# FINALMOTHERBOARD__morefinal.net
KiCad netlist of a schematic drawn in EAGLE
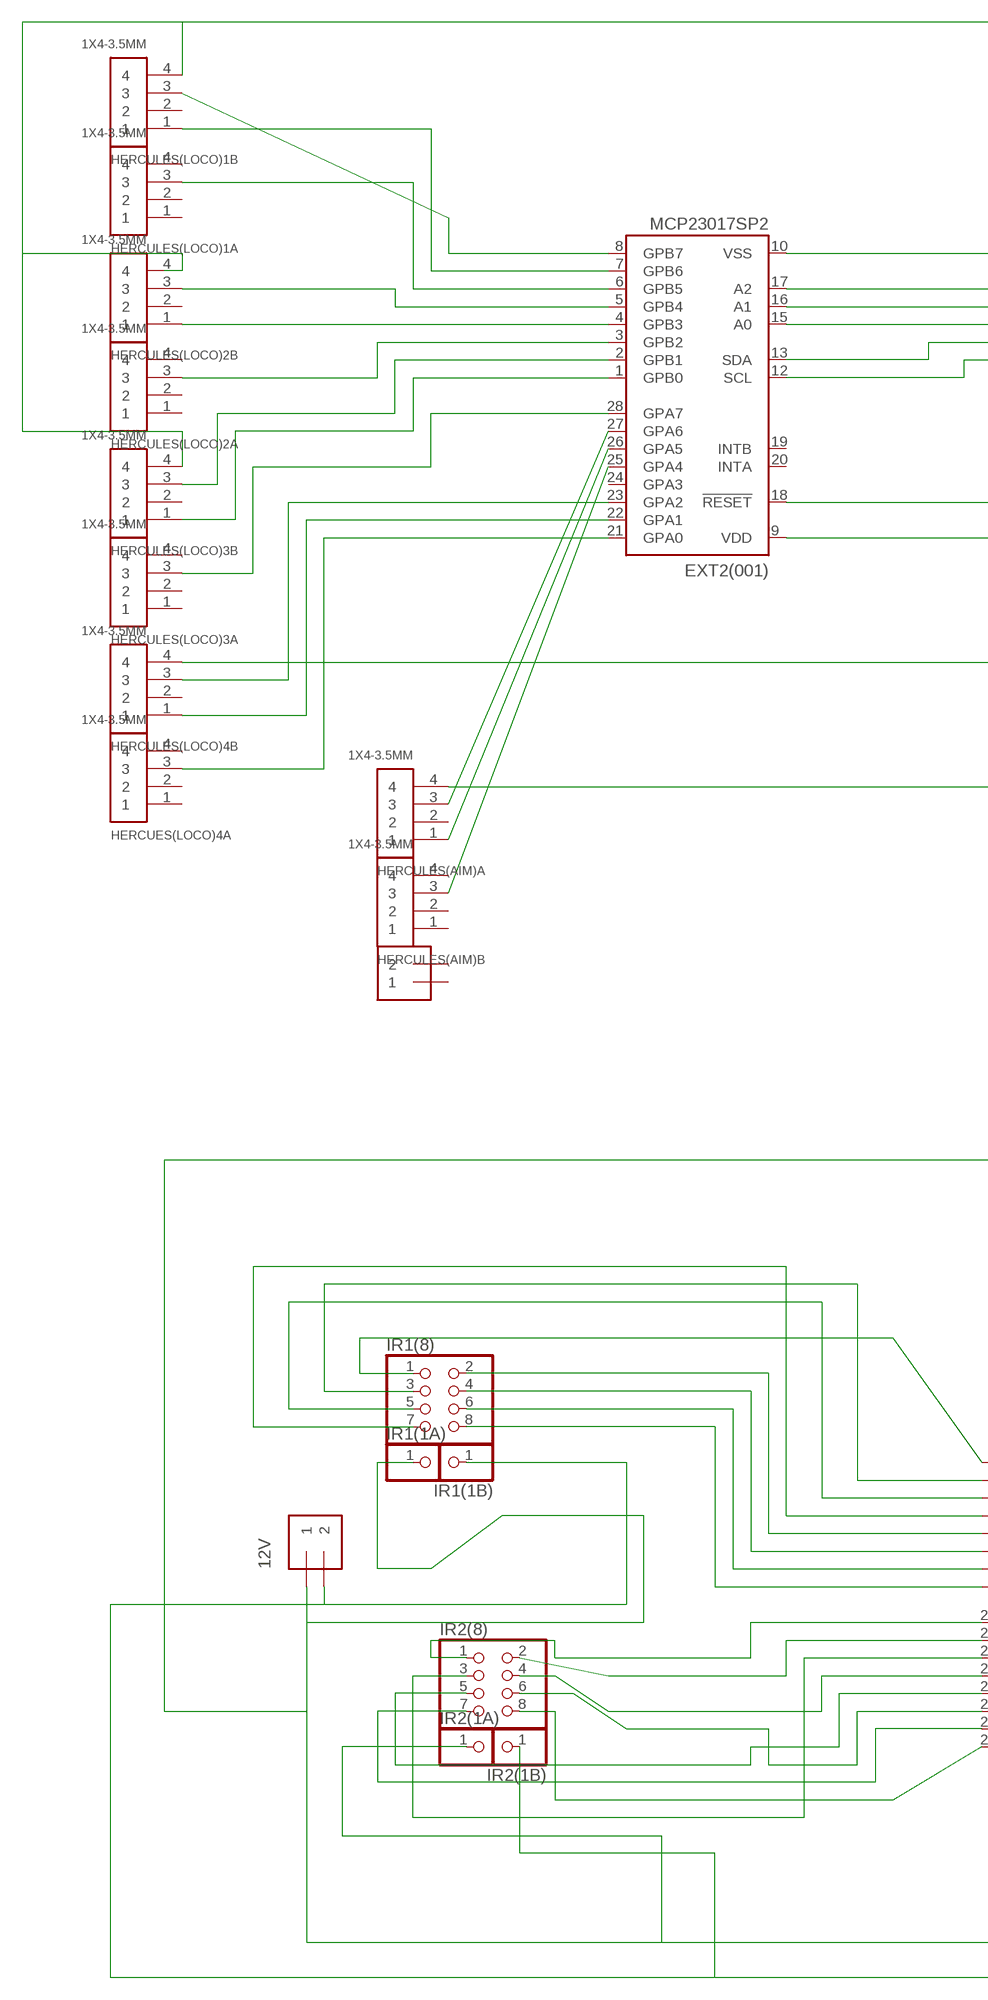
[diagram p0: schematic, sheet 1, part 1 of 2]
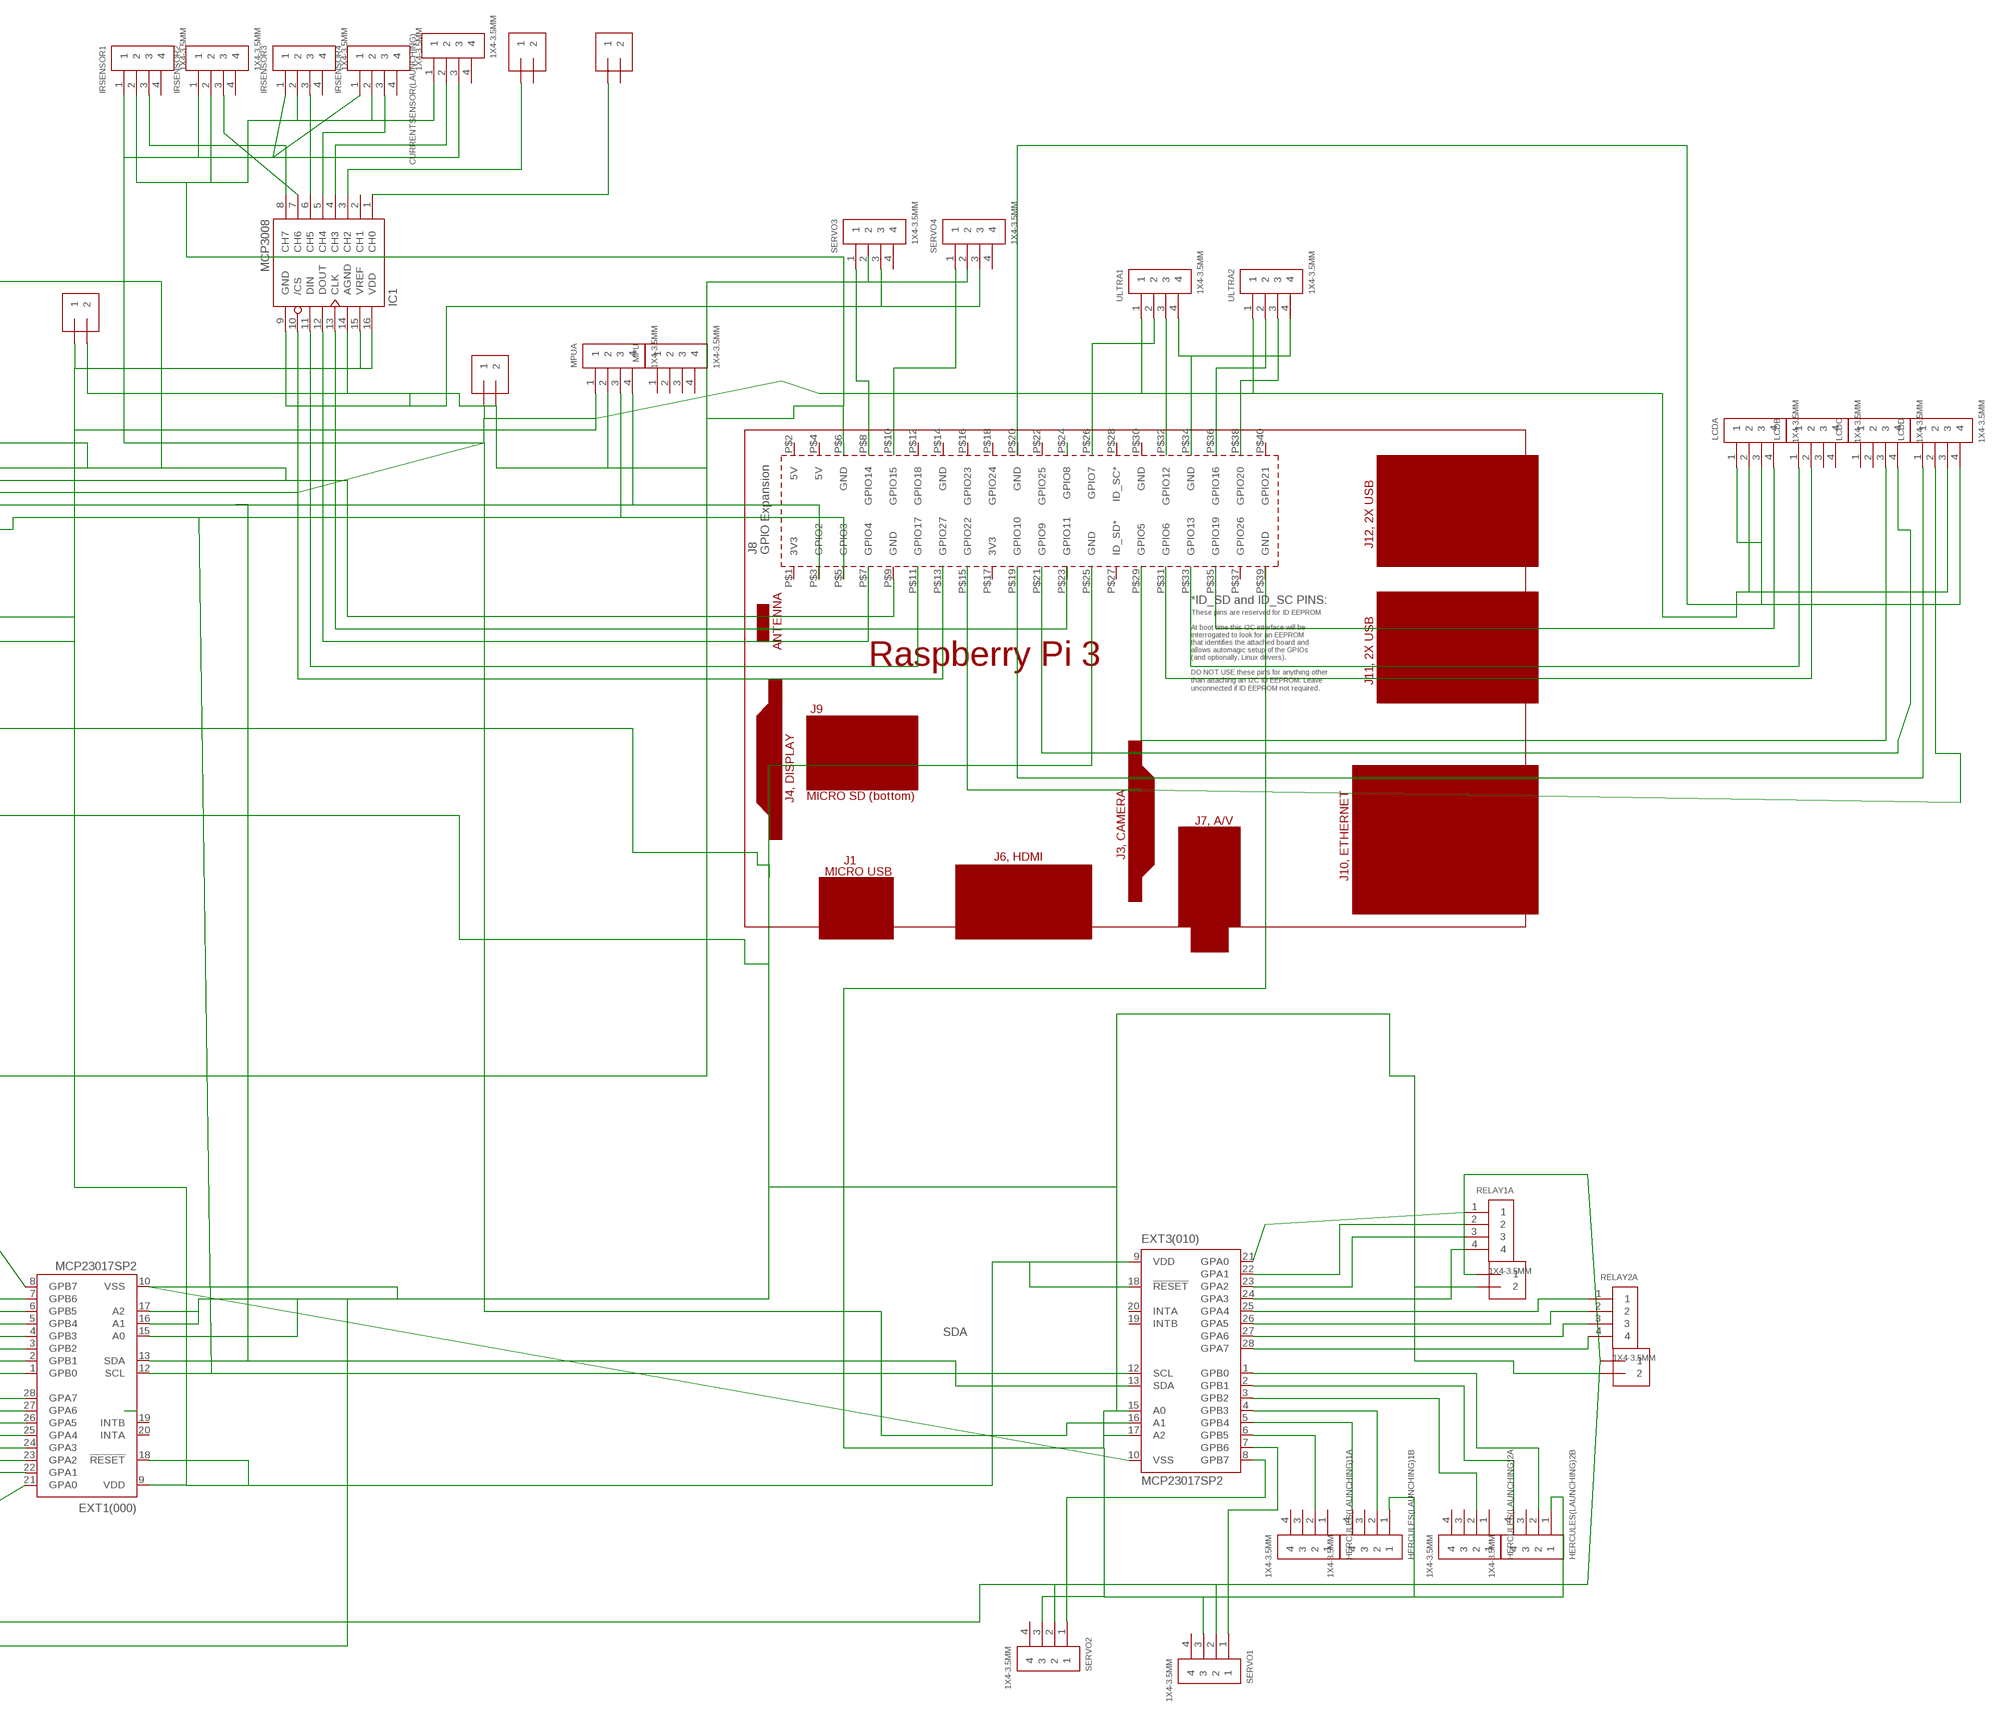
[diagram p1: schematic, sheet 1, part 2 of 2]

(export (version "E")
  (design (tool "Eeschema 10.0.6"))
  (components
    (comp (ref "3.3V")
      (value "1X2-3.5MM")
      (footprint "eagle-import:1X2-3.5MM")
      (libsource (lib "eagle-import") (part "1X2-3.5MM"))
    )
    (comp (ref "5V")
      (value "1X2-3.5MM")
      (footprint "eagle-import:1X2-3.5MM")
      (libsource (lib "eagle-import") (part "1X2-3.5MM"))
    )
    (comp (ref "12V")
      (value "1X2-3.5MM")
      (footprint "eagle-import:1X2-3.5MM")
      (libsource (lib "eagle-import") (part "1X2-3.5MM"))
    )
    (comp (ref "CURRENTSENSOR(LAUNCHING)")
      (value "1X4-3.5MM")
      (footprint "eagle-import:1X04-3.5MM")
      (libsource (lib "eagle-import") (part "1X4-3.5MM"))
    )
    (comp (ref "EXT1(000)")
      (value "MCP23017SP2")
      (footprint "eagle-import:DIL28-3-ROUND")
      (libsource (lib "eagle-import") (part "MCP23017SP2"))
    )
    (comp (ref "EXT2(001)")
      (value "MCP23017SP2")
      (footprint "eagle-import:DIL28-3-ROUND")
      (libsource (lib "eagle-import") (part "MCP23017SP2"))
    )
    (comp (ref "EXT3(010)")
      (value "MCP23017SP2")
      (footprint "eagle-import:DIL28-3-ROUND")
      (libsource (lib "eagle-import") (part "MCP23017SP2"))
    )
    (comp (ref "HERCUES(LOCO)4A")
      (value "1X4-3.5MM")
      (footprint "eagle-import:1X04-3.5MM")
      (libsource (lib "eagle-import") (part "1X4-3.5MM"))
    )
    (comp (ref "HERCULES(AIM)A")
      (value "1X4-3.5MM")
      (footprint "eagle-import:1X04-3.5MM")
      (libsource (lib "eagle-import") (part "1X4-3.5MM"))
    )
    (comp (ref "HERCULES(AIM)B")
      (value "1X4-3.5MM")
      (footprint "eagle-import:1X04-3.5MM")
      (libsource (lib "eagle-import") (part "1X4-3.5MM"))
    )
    (comp (ref "HERCULES(AIM)C")
      (value "1X2-3.5MM")
      (footprint "eagle-import:1X2-3.5MM")
      (libsource (lib "eagle-import") (part "1X2-3.5MM"))
    )
    (comp (ref "HERCULES(LAUNCHING)1A")
      (value "1X4-3.5MM")
      (footprint "eagle-import:1X04-3.5MM")
      (libsource (lib "eagle-import") (part "1X4-3.5MM"))
    )
    (comp (ref "HERCULES(LAUNCHING)1B")
      (value "1X4-3.5MM")
      (footprint "eagle-import:1X04-3.5MM")
      (libsource (lib "eagle-import") (part "1X4-3.5MM"))
    )
    (comp (ref "HERCULES(LAUNCHING)2A")
      (value "1X4-3.5MM")
      (footprint "eagle-import:1X04-3.5MM")
      (libsource (lib "eagle-import") (part "1X4-3.5MM"))
    )
    (comp (ref "HERCULES(LAUNCHING)2B")
      (value "1X4-3.5MM")
      (footprint "eagle-import:1X04-3.5MM")
      (libsource (lib "eagle-import") (part "1X4-3.5MM"))
    )
    (comp (ref "HERCULES(LOCO)1A")
      (value "1X4-3.5MM")
      (footprint "eagle-import:1X04-3.5MM")
      (libsource (lib "eagle-import") (part "1X4-3.5MM"))
    )
    (comp (ref "HERCULES(LOCO)1B")
      (value "1X4-3.5MM")
      (footprint "eagle-import:1X04-3.5MM")
      (libsource (lib "eagle-import") (part "1X4-3.5MM"))
    )
    (comp (ref "HERCULES(LOCO)2A")
      (value "1X4-3.5MM")
      (footprint "eagle-import:1X04-3.5MM")
      (libsource (lib "eagle-import") (part "1X4-3.5MM"))
    )
    (comp (ref "HERCULES(LOCO)2B")
      (value "1X4-3.5MM")
      (footprint "eagle-import:1X04-3.5MM")
      (libsource (lib "eagle-import") (part "1X4-3.5MM"))
    )
    (comp (ref "HERCULES(LOCO)3A")
      (value "1X4-3.5MM")
      (footprint "eagle-import:1X04-3.5MM")
      (libsource (lib "eagle-import") (part "1X4-3.5MM"))
    )
    (comp (ref "HERCULES(LOCO)3B")
      (value "1X4-3.5MM")
      (footprint "eagle-import:1X04-3.5MM")
      (libsource (lib "eagle-import") (part "1X4-3.5MM"))
    )
    (comp (ref "HERCULES(LOCO)4B")
      (value "1X4-3.5MM")
      (footprint "eagle-import:1X04-3.5MM")
      (libsource (lib "eagle-import") (part "1X4-3.5MM"))
    )
    (comp (ref "IC1")
      (value "MCP3008")
      (footprint "eagle-import:DIL16")
      (libsource (lib "eagle-import") (part "MCP3008"))
    )
    (comp (ref "IR(LOCO)1ANALOG")
      (value "1X2-3.5MM")
      (footprint "eagle-import:1X2-3.5MM")
      (libsource (lib "eagle-import") (part "1X2-3.5MM"))
    )
    (comp (ref "IR(LOCO)2ANALOG")
      (value "1X2-3.5MM")
      (footprint "eagle-import:1X2-3.5MM")
      (libsource (lib "eagle-import") (part "1X2-3.5MM"))
    )
    (comp (ref "IR1(1A)")
      (value "PINHD-1X1")
      (footprint "eagle-import:1X01")
      (libsource (lib "eagle-import") (part "PINHD-1X1"))
    )
    (comp (ref "IR1(1B)")
      (value "PINHD-1X1")
      (footprint "eagle-import:1X01")
      (libsource (lib "eagle-import") (part "PINHD-1X1"))
    )
    (comp (ref "IR1(8)")
      (value "PINHD-2X4")
      (footprint "eagle-import:2X04")
      (libsource (lib "eagle-import") (part "PINHD-2X4"))
    )
    (comp (ref "IR2(1A)")
      (value "PINHD-1X1")
      (footprint "eagle-import:1X01")
      (libsource (lib "eagle-import") (part "PINHD-1X1"))
    )
    (comp (ref "IR2(1B)")
      (value "PINHD-1X1")
      (footprint "eagle-import:1X01")
      (libsource (lib "eagle-import") (part "PINHD-1X1"))
    )
    (comp (ref "IR2(8)")
      (value "PINHD-2X4")
      (footprint "eagle-import:2X04")
      (libsource (lib "eagle-import") (part "PINHD-2X4"))
    )
    (comp (ref "IRSENSOR1")
      (value "1X4-3.5MM")
      (footprint "eagle-import:1X04-3.5MM")
      (libsource (lib "eagle-import") (part "1X4-3.5MM"))
    )
    (comp (ref "IRSENSOR2")
      (value "1X4-3.5MM")
      (footprint "eagle-import:1X04-3.5MM")
      (libsource (lib "eagle-import") (part "1X4-3.5MM"))
    )
    (comp (ref "IRSENSOR3")
      (value "1X4-3.5MM")
      (footprint "eagle-import:1X04-3.5MM")
      (libsource (lib "eagle-import") (part "1X4-3.5MM"))
    )
    (comp (ref "IRSENSOR4")
      (value "1X4-3.5MM")
      (footprint "eagle-import:1X04-3.5MM")
      (libsource (lib "eagle-import") (part "1X4-3.5MM"))
    )
    (comp (ref "LCDA")
      (value "1X4-3.5MM")
      (footprint "eagle-import:1X04-3.5MM")
      (libsource (lib "eagle-import") (part "1X4-3.5MM"))
    )
    (comp (ref "LCDB")
      (value "1X4-3.5MM")
      (footprint "eagle-import:1X04-3.5MM")
      (libsource (lib "eagle-import") (part "1X4-3.5MM"))
    )
    (comp (ref "LCDC")
      (value "1X4-3.5MM")
      (footprint "eagle-import:1X04-3.5MM")
      (libsource (lib "eagle-import") (part "1X4-3.5MM"))
    )
    (comp (ref "LCDD")
      (value "1X4-3.5MM")
      (footprint "eagle-import:1X04-3.5MM")
      (libsource (lib "eagle-import") (part "1X4-3.5MM"))
    )
    (comp (ref "MPU")
      (value "1X4-3.5MM")
      (footprint "eagle-import:1X04-3.5MM")
      (libsource (lib "eagle-import") (part "1X4-3.5MM"))
    )
    (comp (ref "MPUA")
      (value "1X4-3.5MM")
      (footprint "eagle-import:1X04-3.5MM")
      (libsource (lib "eagle-import") (part "1X4-3.5MM"))
    )
    (comp (ref "PCB1")
      (value "RPI3")
      (footprint "eagle-import:RPI3")
      (libsource (lib "eagle-import") (part "RPI3"))
    )
    (comp (ref "RELAY1A")
      (value "1X4-3.5MM")
      (footprint "eagle-import:1X04-3.5MM")
      (libsource (lib "eagle-import") (part "1X4-3.5MM"))
    )
    (comp (ref "RELAY1B")
      (value "1X2-3.5MM")
      (footprint "eagle-import:1X2-3.5MM")
      (libsource (lib "eagle-import") (part "1X2-3.5MM"))
    )
    (comp (ref "RELAY2A")
      (value "1X4-3.5MM")
      (footprint "eagle-import:1X04-3.5MM")
      (libsource (lib "eagle-import") (part "1X4-3.5MM"))
    )
    (comp (ref "RELAY2B")
      (value "1X2-3.5MM")
      (footprint "eagle-import:1X2-3.5MM")
      (libsource (lib "eagle-import") (part "1X2-3.5MM"))
    )
    (comp (ref "SERVO1")
      (value "1X4-3.5MM")
      (footprint "eagle-import:1X04-3.5MM")
      (libsource (lib "eagle-import") (part "1X4-3.5MM"))
    )
    (comp (ref "SERVO2")
      (value "1X4-3.5MM")
      (footprint "eagle-import:1X04-3.5MM")
      (libsource (lib "eagle-import") (part "1X4-3.5MM"))
    )
    (comp (ref "SERVO3")
      (value "1X4-3.5MM")
      (footprint "eagle-import:1X04-3.5MM")
      (libsource (lib "eagle-import") (part "1X4-3.5MM"))
    )
    (comp (ref "SERVO4")
      (value "1X4-3.5MM")
      (footprint "eagle-import:1X04-3.5MM")
      (libsource (lib "eagle-import") (part "1X4-3.5MM"))
    )
    (comp (ref "ULTRA1")
      (value "1X4-3.5MM")
      (footprint "eagle-import:1X04-3.5MM")
      (libsource (lib "eagle-import") (part "1X4-3.5MM"))
    )
    (comp (ref "ULTRA2")
      (value "1X4-3.5MM")
      (footprint "eagle-import:1X04-3.5MM")
      (libsource (lib "eagle-import") (part "1X4-3.5MM"))
    )
  )
  (nets
    (net (code "1") (name "12V") (class "Default")
      (node (ref "12V") (pin "1") (pinfunction "1_1") (pintype "passive"))
      (node (ref "IR1(1A)") (pin "1") (pinfunction "1_1") (pintype "passive"))
      (node (ref "IR2(1A)") (pin "1") (pinfunction "1_1") (pintype "passive"))
      (node (ref "RELAY1B") (pin "1") (pinfunction "1_1") (pintype "passive"))
      (node (ref "RELAY2B") (pin "1") (pinfunction "1_1") (pintype "passive"))
      (node (ref "SERVO1") (pin "2") (pinfunction "2_2") (pintype "bidirectional"))
      (node (ref "SERVO2") (pin "2") (pinfunction "2_2") (pintype "bidirectional"))
      (node (ref "SERVO3") (pin "2") (pinfunction "2_2") (pintype "bidirectional"))
      (node (ref "SERVO4") (pin "2") (pinfunction "2_2") (pintype "bidirectional"))
    )
    (net (code "2") (name "Net-(EXT1(000)-A0)") (class "Default")
      (node (ref "12V") (pin "2") (pinfunction "2_2") (pintype "passive"))
      (node (ref "EXT1(000)") (pin "10") (pinfunction "VSS_10") (pintype "power_in"))
      (node (ref "EXT1(000)") (pin "15") (pinfunction "A0_15") (pintype "input"))
      (node (ref "EXT1(000)") (pin "16") (pinfunction "A1_16") (pintype "input"))
      (node (ref "EXT1(000)") (pin "17") (pinfunction "A2_17") (pintype "input"))
      (node (ref "EXT3(010)") (pin "10") (pinfunction "VSS_10") (pintype "power_in"))
      (node (ref "EXT3(010)") (pin "15") (pinfunction "A0_15") (pintype "input"))
      (node (ref "EXT3(010)") (pin "17") (pinfunction "A2_17") (pintype "input"))
      (node (ref "HERCULES(AIM)A") (pin "4") (pinfunction "4_4") (pintype "bidirectional"))
      (node (ref "HERCULES(LAUNCHING)1B") (pin "1") (pinfunction "1_1") (pintype "bidirectional"))
      (node (ref "HERCULES(LAUNCHING)2B") (pin "1") (pinfunction "1_1") (pintype "bidirectional"))
      (node (ref "HERCULES(LOCO)4B") (pin "4") (pinfunction "4_4") (pintype "bidirectional"))
      (node (ref "IR1(1B)") (pin "1") (pinfunction "1_1") (pintype "passive"))
      (node (ref "IR2(1B)") (pin "1") (pinfunction "1_1") (pintype "passive"))
      (node (ref "PCB1") (pin "P$25") (pinfunction "GND_P$25") (pintype "bidirectional"))
      (node (ref "RELAY1B") (pin "2") (pinfunction "2_2") (pintype "passive"))
      (node (ref "RELAY2B") (pin "2") (pinfunction "2_2") (pintype "passive"))
      (node (ref "SERVO1") (pin "3") (pinfunction "3_3") (pintype "bidirectional"))
      (node (ref "SERVO2") (pin "3") (pinfunction "3_3") (pintype "bidirectional"))
    )
    (net (code "3") (name "Net-(EXT1(000)-GPA0)") (class "Default")
      (node (ref "EXT1(000)") (pin "21") (pinfunction "GPA0_21") (pintype "bidirectional"))
      (node (ref "IR2(8)") (pin "8") (pinfunction "8_8") (pintype "passive"))
    )
    (net (code "4") (name "Net-(EXT1(000)-GPA1)") (class "Default")
      (node (ref "EXT1(000)") (pin "22") (pinfunction "GPA1_22") (pintype "bidirectional"))
      (node (ref "IR2(8)") (pin "7") (pinfunction "7_7") (pintype "passive"))
    )
    (net (code "5") (name "Net-(EXT1(000)-GPA2)") (class "Default")
      (node (ref "EXT1(000)") (pin "23") (pinfunction "GPA2_23") (pintype "bidirectional"))
      (node (ref "IR2(8)") (pin "6") (pinfunction "6_6") (pintype "passive"))
    )
    (net (code "6") (name "Net-(EXT1(000)-GPA3)") (class "Default")
      (node (ref "EXT1(000)") (pin "24") (pinfunction "GPA3_24") (pintype "bidirectional"))
      (node (ref "IR2(8)") (pin "5") (pinfunction "5_5") (pintype "passive"))
    )
    (net (code "7") (name "Net-(EXT1(000)-GPA4)") (class "Default")
      (node (ref "EXT1(000)") (pin "25") (pinfunction "GPA4_25") (pintype "bidirectional"))
      (node (ref "IR2(8)") (pin "4") (pinfunction "4_4") (pintype "passive"))
    )
    (net (code "8") (name "Net-(EXT1(000)-GPA5)") (class "Default")
      (node (ref "EXT1(000)") (pin "26") (pinfunction "GPA5_26") (pintype "bidirectional"))
      (node (ref "IR2(8)") (pin "3") (pinfunction "3_3") (pintype "passive"))
    )
    (net (code "9") (name "Net-(EXT1(000)-GPA6)") (class "Default")
      (node (ref "EXT1(000)") (pin "27") (pinfunction "GPA6_27") (pintype "bidirectional"))
      (node (ref "IR2(8)") (pin "2") (pinfunction "2_2") (pintype "passive"))
    )
    (net (code "10") (name "Net-(EXT1(000)-GPA7)") (class "Default")
      (node (ref "EXT1(000)") (pin "28") (pinfunction "GPA7_28") (pintype "bidirectional"))
      (node (ref "IR2(8)") (pin "1") (pinfunction "1_1") (pintype "passive"))
    )
    (net (code "11") (name "Net-(EXT1(000)-GPB0)") (class "Default")
      (node (ref "EXT1(000)") (pin "1") (pinfunction "GPB0_1") (pintype "bidirectional"))
      (node (ref "IR1(8)") (pin "8") (pinfunction "8_8") (pintype "passive"))
    )
    (net (code "12") (name "Net-(EXT1(000)-GPB1)") (class "Default")
      (node (ref "EXT1(000)") (pin "2") (pinfunction "GPB1_2") (pintype "bidirectional"))
      (node (ref "IR1(8)") (pin "6") (pinfunction "6_6") (pintype "passive"))
    )
    (net (code "13") (name "Net-(EXT1(000)-GPB2)") (class "Default")
      (node (ref "EXT1(000)") (pin "3") (pinfunction "GPB2_3") (pintype "bidirectional"))
      (node (ref "IR1(8)") (pin "4") (pinfunction "4_4") (pintype "passive"))
    )
    (net (code "14") (name "Net-(EXT1(000)-GPB3)") (class "Default")
      (node (ref "EXT1(000)") (pin "4") (pinfunction "GPB3_4") (pintype "bidirectional"))
      (node (ref "IR1(8)") (pin "2") (pinfunction "2_2") (pintype "passive"))
    )
    (net (code "15") (name "Net-(EXT1(000)-GPB4)") (class "Default")
      (node (ref "EXT1(000)") (pin "5") (pinfunction "GPB4_5") (pintype "bidirectional"))
      (node (ref "IR1(8)") (pin "7") (pinfunction "7_7") (pintype "passive"))
    )
    (net (code "16") (name "Net-(EXT1(000)-GPB5)") (class "Default")
      (node (ref "EXT1(000)") (pin "6") (pinfunction "GPB5_6") (pintype "bidirectional"))
      (node (ref "IR1(8)") (pin "5") (pinfunction "5_5") (pintype "passive"))
    )
    (net (code "17") (name "Net-(EXT1(000)-GPB6)") (class "Default")
      (node (ref "EXT1(000)") (pin "7") (pinfunction "GPB6_7") (pintype "bidirectional"))
      (node (ref "IR1(8)") (pin "3") (pinfunction "3_3") (pintype "passive"))
    )
    (net (code "18") (name "Net-(EXT1(000)-GPB7)") (class "Default")
      (node (ref "EXT1(000)") (pin "8") (pinfunction "GPB7_8") (pintype "bidirectional"))
      (node (ref "IR1(8)") (pin "1") (pinfunction "1_1") (pintype "passive"))
    )
    (net (code "19") (name "Net-(EXT1(000)-SCL)") (class "Default")
      (node (ref "EXT1(000)") (pin "12") (pinfunction "SCL_12") (pintype "input"))
      (node (ref "EXT2(001)") (pin "12") (pinfunction "SCL_12") (pintype "input"))
      (node (ref "EXT3(010)") (pin "12") (pinfunction "SCL_12") (pintype "input"))
      (node (ref "MPUA") (pin "3") (pinfunction "3_3") (pintype "bidirectional"))
      (node (ref "PCB1") (pin "P$5") (pinfunction "GPIO3_P$5") (pintype "bidirectional"))
    )
    (net (code "20") (name "Net-(EXT1(000)-VDD)") (class "Default")
      (node (ref "3.3V") (pin "1") (pinfunction "1_1") (pintype "passive"))
      (node (ref "EXT1(000)") (pin "18") (pinfunction "~{RESET}_18") (pintype "input"))
      (node (ref "EXT1(000)") (pin "9") (pinfunction "VDD_9") (pintype "power_in"))
      (node (ref "EXT2(001)") (pin "18") (pinfunction "~{RESET}_18") (pintype "input"))
      (node (ref "EXT2(001)") (pin "9") (pinfunction "VDD_9") (pintype "power_in"))
      (node (ref "EXT3(010)") (pin "18") (pinfunction "~{RESET}_18") (pintype "input"))
      (node (ref "EXT3(010)") (pin "9") (pinfunction "VDD_9") (pintype "power_in"))
      (node (ref "IC1") (pin "15") (pinfunction "VREF_15") (pintype "input"))
      (node (ref "IC1") (pin "16") (pinfunction "VDD_16") (pintype "power_in"))
      (node (ref "MPUA") (pin "1") (pinfunction "1_1") (pintype "bidirectional"))
    )
    (net (code "21") (name "Net-(EXT2(001)-A0)") (class "Default")
      (node (ref "5V") (pin "1") (pinfunction "1_1") (pintype "passive"))
      (node (ref "CURRENTSENSOR(LAUNCHING)") (pin "3") (pinfunction "3_3") (pintype "bidirectional"))
      (node (ref "EXT2(001)") (pin "15") (pinfunction "A0_15") (pintype "input"))
      (node (ref "EXT3(010)") (pin "16") (pinfunction "A1_16") (pintype "input"))
      (node (ref "IRSENSOR1") (pin "1") (pinfunction "1_1") (pintype "bidirectional"))
      (node (ref "IRSENSOR2") (pin "1") (pinfunction "1_1") (pintype "bidirectional"))
      (node (ref "IRSENSOR3") (pin "1") (pinfunction "1_1") (pintype "bidirectional"))
      (node (ref "IRSENSOR4") (pin "1") (pinfunction "1_1") (pintype "bidirectional"))
      (node (ref "LCDA") (pin "2") (pinfunction "2_2") (pintype "bidirectional"))
      (node (ref "LCDD") (pin "3") (pinfunction "3_3") (pintype "bidirectional"))
      (node (ref "ULTRA1") (pin "1") (pinfunction "1_1") (pintype "bidirectional"))
      (node (ref "ULTRA2") (pin "1") (pinfunction "1_1") (pintype "bidirectional"))
    )
    (net (code "22") (name "Net-(EXT2(001)-A1)") (class "Default")
      (node (ref "EXT2(001)") (pin "10") (pinfunction "VSS_10") (pintype "power_in"))
      (node (ref "EXT2(001)") (pin "16") (pinfunction "A1_16") (pintype "input"))
      (node (ref "EXT2(001)") (pin "17") (pinfunction "A2_17") (pintype "input"))
      (node (ref "HERCULES(LOCO)1B") (pin "4") (pinfunction "4_4") (pintype "bidirectional"))
      (node (ref "HERCULES(LOCO)2B") (pin "4") (pinfunction "4_4") (pintype "bidirectional"))
      (node (ref "HERCULES(LOCO)3B") (pin "4") (pinfunction "4_4") (pintype "bidirectional"))
      (node (ref "PCB1") (pin "P$9") (pinfunction "GND_P$9") (pintype "bidirectional"))
    )
    (net (code "23") (name "Net-(EXT2(001)-GPA0)") (class "Default")
      (node (ref "EXT2(001)") (pin "21") (pinfunction "GPA0_21") (pintype "bidirectional"))
      (node (ref "HERCUES(LOCO)4A") (pin "3") (pinfunction "3_3") (pintype "bidirectional"))
    )
    (net (code "24") (name "Net-(EXT2(001)-GPA1)") (class "Default")
      (node (ref "EXT2(001)") (pin "22") (pinfunction "GPA1_22") (pintype "bidirectional"))
      (node (ref "HERCULES(LOCO)4B") (pin "1") (pinfunction "1_1") (pintype "bidirectional"))
    )
    (net (code "25") (name "Net-(EXT2(001)-GPA2)") (class "Default")
      (node (ref "EXT2(001)") (pin "23") (pinfunction "GPA2_23") (pintype "bidirectional"))
      (node (ref "HERCULES(LOCO)4B") (pin "3") (pinfunction "3_3") (pintype "bidirectional"))
    )
    (net (code "26") (name "Net-(EXT2(001)-GPA4)") (class "Default")
      (node (ref "EXT2(001)") (pin "25") (pinfunction "GPA4_25") (pintype "bidirectional"))
      (node (ref "HERCULES(AIM)B") (pin "3") (pinfunction "3_3") (pintype "bidirectional"))
    )
    (net (code "27") (name "Net-(EXT2(001)-GPA5)") (class "Default")
      (node (ref "EXT2(001)") (pin "26") (pinfunction "GPA5_26") (pintype "bidirectional"))
      (node (ref "HERCULES(AIM)A") (pin "1") (pinfunction "1_1") (pintype "bidirectional"))
    )
    (net (code "28") (name "Net-(EXT2(001)-GPA6)") (class "Default")
      (node (ref "EXT2(001)") (pin "27") (pinfunction "GPA6_27") (pintype "bidirectional"))
      (node (ref "HERCULES(AIM)A") (pin "3") (pinfunction "3_3") (pintype "bidirectional"))
    )
    (net (code "29") (name "Net-(EXT2(001)-GPA7)") (class "Default")
      (node (ref "EXT2(001)") (pin "28") (pinfunction "GPA7_28") (pintype "bidirectional"))
      (node (ref "HERCULES(LOCO)3A") (pin "3") (pinfunction "3_3") (pintype "bidirectional"))
    )
    (net (code "30") (name "Net-(EXT2(001)-GPB0)") (class "Default")
      (node (ref "EXT2(001)") (pin "1") (pinfunction "GPB0_1") (pintype "bidirectional"))
      (node (ref "HERCULES(LOCO)3B") (pin "1") (pinfunction "1_1") (pintype "bidirectional"))
    )
    (net (code "31") (name "Net-(EXT2(001)-GPB1)") (class "Default")
      (node (ref "EXT2(001)") (pin "2") (pinfunction "GPB1_2") (pintype "bidirectional"))
      (node (ref "HERCULES(LOCO)3B") (pin "3") (pinfunction "3_3") (pintype "bidirectional"))
    )
    (net (code "32") (name "Net-(EXT2(001)-GPB2)") (class "Default")
      (node (ref "EXT2(001)") (pin "3") (pinfunction "GPB2_3") (pintype "bidirectional"))
      (node (ref "HERCULES(LOCO)2A") (pin "3") (pinfunction "3_3") (pintype "bidirectional"))
    )
    (net (code "33") (name "Net-(EXT2(001)-GPB3)") (class "Default")
      (node (ref "EXT2(001)") (pin "4") (pinfunction "GPB3_4") (pintype "bidirectional"))
      (node (ref "HERCULES(LOCO)2B") (pin "1") (pinfunction "1_1") (pintype "bidirectional"))
    )
    (net (code "34") (name "Net-(EXT2(001)-GPB4)") (class "Default")
      (node (ref "EXT2(001)") (pin "5") (pinfunction "GPB4_5") (pintype "bidirectional"))
      (node (ref "HERCULES(LOCO)2B") (pin "3") (pinfunction "3_3") (pintype "bidirectional"))
    )
    (net (code "35") (name "Net-(EXT2(001)-GPB5)") (class "Default")
      (node (ref "EXT2(001)") (pin "6") (pinfunction "GPB5_6") (pintype "bidirectional"))
      (node (ref "HERCULES(LOCO)1A") (pin "3") (pinfunction "3_3") (pintype "bidirectional"))
    )
    (net (code "36") (name "Net-(EXT2(001)-GPB6)") (class "Default")
      (node (ref "EXT2(001)") (pin "7") (pinfunction "GPB6_7") (pintype "bidirectional"))
      (node (ref "HERCULES(LOCO)1B") (pin "1") (pinfunction "1_1") (pintype "bidirectional"))
    )
    (net (code "37") (name "Net-(EXT2(001)-GPB7)") (class "Default")
      (node (ref "EXT2(001)") (pin "8") (pinfunction "GPB7_8") (pintype "bidirectional"))
      (node (ref "HERCULES(LOCO)1B") (pin "3") (pinfunction "3_3") (pintype "bidirectional"))
    )
    (net (code "38") (name "Net-(EXT3(010)-GPA0)") (class "Default")
      (node (ref "EXT3(010)") (pin "21") (pinfunction "GPA0_21") (pintype "bidirectional"))
      (node (ref "RELAY1A") (pin "1") (pinfunction "1_1") (pintype "bidirectional"))
    )
    (net (code "39") (name "Net-(EXT3(010)-GPA1)") (class "Default")
      (node (ref "EXT3(010)") (pin "22") (pinfunction "GPA1_22") (pintype "bidirectional"))
      (node (ref "RELAY1A") (pin "2") (pinfunction "2_2") (pintype "bidirectional"))
    )
    (net (code "40") (name "Net-(EXT3(010)-GPA2)") (class "Default")
      (node (ref "EXT3(010)") (pin "23") (pinfunction "GPA2_23") (pintype "bidirectional"))
      (node (ref "RELAY1A") (pin "3") (pinfunction "3_3") (pintype "bidirectional"))
    )
    (net (code "41") (name "Net-(EXT3(010)-GPA3)") (class "Default")
      (node (ref "EXT3(010)") (pin "24") (pinfunction "GPA3_24") (pintype "bidirectional"))
      (node (ref "RELAY1A") (pin "4") (pinfunction "4_4") (pintype "bidirectional"))
    )
    (net (code "42") (name "Net-(EXT3(010)-GPA4)") (class "Default")
      (node (ref "EXT3(010)") (pin "25") (pinfunction "GPA4_25") (pintype "bidirectional"))
      (node (ref "RELAY2A") (pin "1") (pinfunction "1_1") (pintype "bidirectional"))
    )
    (net (code "43") (name "Net-(EXT3(010)-GPA5)") (class "Default")
      (node (ref "EXT3(010)") (pin "26") (pinfunction "GPA5_26") (pintype "bidirectional"))
      (node (ref "RELAY2A") (pin "2") (pinfunction "2_2") (pintype "bidirectional"))
    )
    (net (code "44") (name "Net-(EXT3(010)-GPA6)") (class "Default")
      (node (ref "EXT3(010)") (pin "27") (pinfunction "GPA6_27") (pintype "bidirectional"))
      (node (ref "RELAY2A") (pin "3") (pinfunction "3_3") (pintype "bidirectional"))
    )
    (net (code "45") (name "Net-(EXT3(010)-GPA7)") (class "Default")
      (node (ref "EXT3(010)") (pin "28") (pinfunction "GPA7_28") (pintype "bidirectional"))
      (node (ref "RELAY2A") (pin "4") (pinfunction "4_4") (pintype "bidirectional"))
    )
    (net (code "46") (name "Net-(EXT3(010)-GPB0)") (class "Default")
      (node (ref "EXT3(010)") (pin "1") (pinfunction "GPB0_1") (pintype "bidirectional"))
      (node (ref "HERCULES(LAUNCHING)2B") (pin "2") (pinfunction "2_2") (pintype "bidirectional"))
    )
    (net (code "47") (name "Net-(EXT3(010)-GPB1)") (class "Default")
      (node (ref "EXT3(010)") (pin "2") (pinfunction "GPB1_2") (pintype "bidirectional"))
      (node (ref "HERCULES(LAUNCHING)2B") (pin "4") (pinfunction "4_4") (pintype "bidirectional"))
    )
    (net (code "48") (name "Net-(EXT3(010)-GPB2)") (class "Default")
      (node (ref "EXT3(010)") (pin "3") (pinfunction "GPB2_3") (pintype "bidirectional"))
      (node (ref "HERCULES(LAUNCHING)2A") (pin "2") (pinfunction "2_2") (pintype "bidirectional"))
    )
    (net (code "49") (name "Net-(EXT3(010)-GPB3)") (class "Default")
      (node (ref "EXT3(010)") (pin "4") (pinfunction "GPB3_4") (pintype "bidirectional"))
      (node (ref "HERCULES(LAUNCHING)1B") (pin "2") (pinfunction "2_2") (pintype "bidirectional"))
    )
    (net (code "50") (name "Net-(EXT3(010)-GPB4)") (class "Default")
      (node (ref "EXT3(010)") (pin "5") (pinfunction "GPB4_5") (pintype "bidirectional"))
      (node (ref "HERCULES(LAUNCHING)1B") (pin "4") (pinfunction "4_4") (pintype "bidirectional"))
    )
    (net (code "51") (name "Net-(EXT3(010)-GPB5)") (class "Default")
      (node (ref "EXT3(010)") (pin "6") (pinfunction "GPB5_6") (pintype "bidirectional"))
      (node (ref "HERCULES(LAUNCHING)1A") (pin "2") (pinfunction "2_2") (pintype "bidirectional"))
    )
    (net (code "52") (name "Net-(EXT3(010)-GPB6)") (class "Default")
      (node (ref "EXT3(010)") (pin "7") (pinfunction "GPB6_7") (pintype "bidirectional"))
      (node (ref "SERVO1") (pin "1") (pinfunction "1_1") (pintype "bidirectional"))
    )
    (net (code "53") (name "Net-(EXT3(010)-GPB7)") (class "Default")
      (node (ref "EXT3(010)") (pin "8") (pinfunction "GPB7_8") (pintype "bidirectional"))
      (node (ref "SERVO2") (pin "1") (pinfunction "1_1") (pintype "bidirectional"))
    )
    (net (code "54") (name "Net-(IC1-AGND)") (class "Default")
      (node (ref "3.3V") (pin "2") (pinfunction "2_2") (pintype "passive"))
      (node (ref "5V") (pin "2") (pinfunction "2_2") (pintype "passive"))
      (node (ref "CURRENTSENSOR(LAUNCHING)") (pin "1") (pinfunction "1_1") (pintype "bidirectional"))
      (node (ref "IC1") (pin "14") (pinfunction "AGND_14") (pintype "power_in"))
      (node (ref "IC1") (pin "9") (pinfunction "GND_9") (pintype "power_in"))
      (node (ref "IRSENSOR1") (pin "2") (pinfunction "2_2") (pintype "bidirectional"))
      (node (ref "IRSENSOR2") (pin "2") (pinfunction "2_2") (pintype "bidirectional"))
      (node (ref "IRSENSOR3") (pin "2") (pinfunction "2_2") (pintype "bidirectional"))
      (node (ref "IRSENSOR4") (pin "2") (pinfunction "2_2") (pintype "bidirectional"))
      (node (ref "MPUA") (pin "2") (pinfunction "2_2") (pintype "bidirectional"))
      (node (ref "PCB1") (pin "P$6") (pinfunction "GND_P$6") (pintype "bidirectional"))
      (node (ref "SERVO3") (pin "3") (pinfunction "3_3") (pintype "bidirectional"))
      (node (ref "SERVO4") (pin "3") (pinfunction "3_3") (pintype "bidirectional"))
    )
    (net (code "55") (name "Net-(IC1-CH0)") (class "Default")
      (node (ref "IC1") (pin "1") (pinfunction "CH0_1") (pintype "input"))
      (node (ref "IR(LOCO)2ANALOG") (pin "1") (pinfunction "1_1") (pintype "passive"))
    )
    (net (code "56") (name "Net-(IC1-CH2)") (class "Default")
      (node (ref "IC1") (pin "3") (pinfunction "CH2_3") (pintype "input"))
      (node (ref "IR(LOCO)1ANALOG") (pin "1") (pinfunction "1_1") (pintype "passive"))
    )
    (net (code "57") (name "Net-(IC1-CH3)") (class "Default")
      (node (ref "CURRENTSENSOR(LAUNCHING)") (pin "2") (pinfunction "2_2") (pintype "bidirectional"))
      (node (ref "IC1") (pin "4") (pinfunction "CH3_4") (pintype "input"))
    )
    (net (code "58") (name "Net-(IC1-CH4)") (class "Default")
      (node (ref "IC1") (pin "5") (pinfunction "CH4_5") (pintype "input"))
      (node (ref "IRSENSOR4") (pin "3") (pinfunction "3_3") (pintype "bidirectional"))
    )
    (net (code "59") (name "Net-(IC1-CH5)") (class "Default")
      (node (ref "IC1") (pin "6") (pinfunction "CH5_6") (pintype "input"))
      (node (ref "IRSENSOR3") (pin "3") (pinfunction "3_3") (pintype "bidirectional"))
    )
    (net (code "60") (name "Net-(IC1-CH6)") (class "Default")
      (node (ref "IC1") (pin "7") (pinfunction "CH6_7") (pintype "input"))
      (node (ref "IRSENSOR2") (pin "3") (pinfunction "3_3") (pintype "bidirectional"))
    )
    (net (code "61") (name "Net-(IC1-CH7)") (class "Default")
      (node (ref "IC1") (pin "8") (pinfunction "CH7_8") (pintype "input"))
      (node (ref "IRSENSOR1") (pin "3") (pinfunction "3_3") (pintype "bidirectional"))
    )
    (net (code "62") (name "Net-(IC1-CLK)") (class "Default")
      (node (ref "IC1") (pin "13") (pinfunction "CLK_13") (pintype "input"))
      (node (ref "PCB1") (pin "P$23") (pinfunction "GPIO11_P$23") (pintype "bidirectional"))
    )
    (net (code "63") (name "Net-(IC1-DIN)") (class "Default")
      (node (ref "IC1") (pin "11") (pinfunction "DIN_11") (pintype "input"))
      (node (ref "PCB1") (pin "P$11") (pinfunction "GPIO17_P$11") (pintype "bidirectional"))
    )
    (net (code "64") (name "Net-(IC1-DOUT)") (class "Default")
      (node (ref "IC1") (pin "12") (pinfunction "DOUT_12") (pintype "output"))
      (node (ref "PCB1") (pin "P$7") (pinfunction "GPIO4_P$7") (pintype "bidirectional"))
    )
    (net (code "65") (name "Net-(IC1-{slash}CS)") (class "Default")
      (node (ref "IC1") (pin "10") (pinfunction "/CS_10") (pintype "input"))
      (node (ref "PCB1") (pin "P$13") (pinfunction "GPIO27_P$13") (pintype "bidirectional"))
    )
    (net (code "66") (name "Net-(LCDA-Pad1)") (class "Default")
      (node (ref "LCDA") (pin "1") (pinfunction "1_1") (pintype "bidirectional"))
      (node (ref "LCDA") (pin "3") (pinfunction "3_3") (pintype "bidirectional"))
      (node (ref "LCDD") (pin "4") (pinfunction "4_4") (pintype "bidirectional"))
    )
    (net (code "67") (name "Net-(PCB1-GND-PadP$34)") (class "Default")
      (node (ref "PCB1") (pin "P$34") (pinfunction "GND_P$34") (pintype "bidirectional"))
      (node (ref "ULTRA1") (pin "4") (pinfunction "4_4") (pintype "bidirectional"))
      (node (ref "ULTRA2") (pin "4") (pinfunction "4_4") (pintype "bidirectional"))
    )
    (net (code "68") (name "Net-(PCB1-GPIO5)") (class "Default")
      (node (ref "LCDC") (pin "3") (pinfunction "3_3") (pintype "bidirectional"))
      (node (ref "PCB1") (pin "P$29") (pinfunction "GPIO5_P$29") (pintype "bidirectional"))
    )
    (net (code "69") (name "Net-(PCB1-GPIO6)") (class "Default")
      (node (ref "LCDB") (pin "2") (pinfunction "2_2") (pintype "bidirectional"))
      (node (ref "PCB1") (pin "P$31") (pinfunction "GPIO6_P$31") (pintype "bidirectional"))
    )
    (net (code "70") (name "Net-(PCB1-GPIO7)") (class "Default")
      (node (ref "PCB1") (pin "P$26") (pinfunction "GPIO7_P$26") (pintype "bidirectional"))
      (node (ref "ULTRA1") (pin "2") (pinfunction "2_2") (pintype "bidirectional"))
    )
    (net (code "71") (name "Net-(PCB1-GPIO9)") (class "Default")
      (node (ref "LCDC") (pin "4") (pinfunction "4_4") (pintype "bidirectional"))
      (node (ref "PCB1") (pin "P$21") (pinfunction "GPIO9_P$21") (pintype "bidirectional"))
    )
    (net (code "72") (name "Net-(PCB1-GPIO10)") (class "Default")
      (node (ref "LCDD") (pin "1") (pinfunction "1_1") (pintype "bidirectional"))
      (node (ref "PCB1") (pin "P$19") (pinfunction "GPIO10_P$19") (pintype "bidirectional"))
    )
    (net (code "73") (name "Net-(PCB1-GPIO12)") (class "Default")
      (node (ref "PCB1") (pin "P$32") (pinfunction "GPIO12_P$32") (pintype "bidirectional"))
      (node (ref "ULTRA1") (pin "3") (pinfunction "3_3") (pintype "bidirectional"))
    )
    (net (code "74") (name "Net-(PCB1-GPIO13)") (class "Default")
      (node (ref "LCDB") (pin "1") (pinfunction "1_1") (pintype "bidirectional"))
      (node (ref "PCB1") (pin "P$33") (pinfunction "GPIO13_P$33") (pintype "bidirectional"))
    )
    (net (code "75") (name "Net-(PCB1-GPIO14)") (class "Default")
      (node (ref "PCB1") (pin "P$8") (pinfunction "GPIO14_P$8") (pintype "bidirectional"))
      (node (ref "SERVO3") (pin "1") (pinfunction "1_1") (pintype "bidirectional"))
    )
    (net (code "76") (name "Net-(PCB1-GPIO15)") (class "Default")
      (node (ref "PCB1") (pin "P$10") (pinfunction "GPIO15_P$10") (pintype "bidirectional"))
      (node (ref "SERVO4") (pin "1") (pinfunction "1_1") (pintype "bidirectional"))
    )
    (net (code "77") (name "Net-(PCB1-GPIO16)") (class "Default")
      (node (ref "PCB1") (pin "P$36") (pinfunction "GPIO16_P$36") (pintype "bidirectional"))
      (node (ref "ULTRA2") (pin "2") (pinfunction "2_2") (pintype "bidirectional"))
    )
    (net (code "78") (name "Net-(PCB1-GPIO19)") (class "Default")
      (node (ref "LCDA") (pin "4") (pinfunction "4_4") (pintype "bidirectional"))
      (node (ref "PCB1") (pin "P$35") (pinfunction "GPIO19_P$35") (pintype "bidirectional"))
    )
    (net (code "79") (name "Net-(PCB1-GPIO20)") (class "Default")
      (node (ref "PCB1") (pin "P$38") (pinfunction "GPIO20_P$38") (pintype "bidirectional"))
      (node (ref "ULTRA2") (pin "3") (pinfunction "3_3") (pintype "bidirectional"))
    )
    (net (code "80") (name "Net-(PCB1-GPIO22)") (class "Default")
      (node (ref "LCDD") (pin "2") (pinfunction "2_2") (pintype "bidirectional"))
      (node (ref "PCB1") (pin "P$15") (pinfunction "GPIO22_P$15") (pintype "bidirectional"))
    )
    (net (code "81") (name "SDA") (class "Default")
      (node (ref "EXT1(000)") (pin "13") (pinfunction "SDA_13") (pintype "bidirectional"))
      (node (ref "EXT2(001)") (pin "13") (pinfunction "SDA_13") (pintype "bidirectional"))
      (node (ref "EXT3(010)") (pin "13") (pinfunction "SDA_13") (pintype "bidirectional"))
      (node (ref "MPUA") (pin "4") (pinfunction "4_4") (pintype "bidirectional"))
      (node (ref "PCB1") (pin "P$3") (pinfunction "GPIO2_P$3") (pintype "bidirectional"))
    )
    (net (code "82") (name "unconnected-(CURRENTSENSOR(LAUNCHING)-Pad4)") (class "Default")
      (node (ref "CURRENTSENSOR(LAUNCHING)") (pin "4") (pinfunction "4_4") (pintype "bidirectional"))
    )
    (net (code "83") (name "unconnected-(EXT1(000)-INTA-Pad20)") (class "Default")
      (node (ref "EXT1(000)") (pin "20") (pinfunction "INTA_20") (pintype "output"))
    )
    (net (code "84") (name "unconnected-(EXT1(000)-INTB-Pad19)") (class "Default")
      (node (ref "EXT1(000)") (pin "19") (pinfunction "INTB_19") (pintype "output"))
    )
    (net (code "85") (name "unconnected-(EXT2(001)-GPA3-Pad24)") (class "Default")
      (node (ref "EXT2(001)") (pin "24") (pinfunction "GPA3_24") (pintype "bidirectional"))
    )
    (net (code "86") (name "unconnected-(EXT2(001)-INTA-Pad20)") (class "Default")
      (node (ref "EXT2(001)") (pin "20") (pinfunction "INTA_20") (pintype "output"))
    )
    (net (code "87") (name "unconnected-(EXT2(001)-INTB-Pad19)") (class "Default")
      (node (ref "EXT2(001)") (pin "19") (pinfunction "INTB_19") (pintype "output"))
    )
    (net (code "88") (name "unconnected-(EXT3(010)-INTA-Pad20)") (class "Default")
      (node (ref "EXT3(010)") (pin "20") (pinfunction "INTA_20") (pintype "output"))
    )
    (net (code "89") (name "unconnected-(EXT3(010)-INTB-Pad19)") (class "Default")
      (node (ref "EXT3(010)") (pin "19") (pinfunction "INTB_19") (pintype "output"))
    )
    (net (code "90") (name "unconnected-(HERCUES(LOCO)4A-Pad1)") (class "Default")
      (node (ref "HERCUES(LOCO)4A") (pin "1") (pinfunction "1_1") (pintype "bidirectional"))
    )
    (net (code "91") (name "unconnected-(HERCUES(LOCO)4A-Pad2)") (class "Default")
      (node (ref "HERCUES(LOCO)4A") (pin "2") (pinfunction "2_2") (pintype "bidirectional"))
    )
    (net (code "92") (name "unconnected-(HERCUES(LOCO)4A-Pad4)") (class "Default")
      (node (ref "HERCUES(LOCO)4A") (pin "4") (pinfunction "4_4") (pintype "bidirectional"))
    )
    (net (code "93") (name "unconnected-(HERCULES(AIM)A-Pad2)") (class "Default")
      (node (ref "HERCULES(AIM)A") (pin "2") (pinfunction "2_2") (pintype "bidirectional"))
    )
    (net (code "94") (name "unconnected-(HERCULES(AIM)B-Pad1)") (class "Default")
      (node (ref "HERCULES(AIM)B") (pin "1") (pinfunction "1_1") (pintype "bidirectional"))
    )
    (net (code "95") (name "unconnected-(HERCULES(AIM)B-Pad2)") (class "Default")
      (node (ref "HERCULES(AIM)B") (pin "2") (pinfunction "2_2") (pintype "bidirectional"))
    )
    (net (code "96") (name "unconnected-(HERCULES(AIM)B-Pad4)") (class "Default")
      (node (ref "HERCULES(AIM)B") (pin "4") (pinfunction "4_4") (pintype "bidirectional"))
    )
    (net (code "97") (name "unconnected-(HERCULES(AIM)C-Pad1)") (class "Default")
      (node (ref "HERCULES(AIM)C") (pin "1") (pinfunction "1_1") (pintype "passive"))
    )
    (net (code "98") (name "unconnected-(HERCULES(AIM)C-Pad2)") (class "Default")
      (node (ref "HERCULES(AIM)C") (pin "2") (pinfunction "2_2") (pintype "passive"))
    )
    (net (code "99") (name "unconnected-(HERCULES(LAUNCHING)1A-Pad1)") (class "Default")
      (node (ref "HERCULES(LAUNCHING)1A") (pin "1") (pinfunction "1_1") (pintype "bidirectional"))
    )
    (net (code "100") (name "unconnected-(HERCULES(LAUNCHING)1A-Pad3)") (class "Default")
      (node (ref "HERCULES(LAUNCHING)1A") (pin "3") (pinfunction "3_3") (pintype "bidirectional"))
    )
    (net (code "101") (name "unconnected-(HERCULES(LAUNCHING)1A-Pad4)") (class "Default")
      (node (ref "HERCULES(LAUNCHING)1A") (pin "4") (pinfunction "4_4") (pintype "bidirectional"))
    )
    (net (code "102") (name "unconnected-(HERCULES(LAUNCHING)1B-Pad3)") (class "Default")
      (node (ref "HERCULES(LAUNCHING)1B") (pin "3") (pinfunction "3_3") (pintype "bidirectional"))
    )
    (net (code "103") (name "unconnected-(HERCULES(LAUNCHING)2A-Pad1)") (class "Default")
      (node (ref "HERCULES(LAUNCHING)2A") (pin "1") (pinfunction "1_1") (pintype "bidirectional"))
    )
    (net (code "104") (name "unconnected-(HERCULES(LAUNCHING)2A-Pad3)") (class "Default")
      (node (ref "HERCULES(LAUNCHING)2A") (pin "3") (pinfunction "3_3") (pintype "bidirectional"))
    )
    (net (code "105") (name "unconnected-(HERCULES(LAUNCHING)2A-Pad4)") (class "Default")
      (node (ref "HERCULES(LAUNCHING)2A") (pin "4") (pinfunction "4_4") (pintype "bidirectional"))
    )
    (net (code "106") (name "unconnected-(HERCULES(LAUNCHING)2B-Pad3)") (class "Default")
      (node (ref "HERCULES(LAUNCHING)2B") (pin "3") (pinfunction "3_3") (pintype "bidirectional"))
    )
    (net (code "107") (name "unconnected-(HERCULES(LOCO)1A-Pad1)") (class "Default")
      (node (ref "HERCULES(LOCO)1A") (pin "1") (pinfunction "1_1") (pintype "bidirectional"))
    )
    (net (code "108") (name "unconnected-(HERCULES(LOCO)1A-Pad2)") (class "Default")
      (node (ref "HERCULES(LOCO)1A") (pin "2") (pinfunction "2_2") (pintype "bidirectional"))
    )
    (net (code "109") (name "unconnected-(HERCULES(LOCO)1A-Pad4)") (class "Default")
      (node (ref "HERCULES(LOCO)1A") (pin "4") (pinfunction "4_4") (pintype "bidirectional"))
    )
    (net (code "110") (name "unconnected-(HERCULES(LOCO)1B-Pad2)") (class "Default")
      (node (ref "HERCULES(LOCO)1B") (pin "2") (pinfunction "2_2") (pintype "bidirectional"))
    )
    (net (code "111") (name "unconnected-(HERCULES(LOCO)2A-Pad1)") (class "Default")
      (node (ref "HERCULES(LOCO)2A") (pin "1") (pinfunction "1_1") (pintype "bidirectional"))
    )
    (net (code "112") (name "unconnected-(HERCULES(LOCO)2A-Pad2)") (class "Default")
      (node (ref "HERCULES(LOCO)2A") (pin "2") (pinfunction "2_2") (pintype "bidirectional"))
    )
    (net (code "113") (name "unconnected-(HERCULES(LOCO)2A-Pad4)") (class "Default")
      (node (ref "HERCULES(LOCO)2A") (pin "4") (pinfunction "4_4") (pintype "bidirectional"))
    )
    (net (code "114") (name "unconnected-(HERCULES(LOCO)2B-Pad2)") (class "Default")
      (node (ref "HERCULES(LOCO)2B") (pin "2") (pinfunction "2_2") (pintype "bidirectional"))
    )
    (net (code "115") (name "unconnected-(HERCULES(LOCO)3A-Pad1)") (class "Default")
      (node (ref "HERCULES(LOCO)3A") (pin "1") (pinfunction "1_1") (pintype "bidirectional"))
    )
    (net (code "116") (name "unconnected-(HERCULES(LOCO)3A-Pad2)") (class "Default")
      (node (ref "HERCULES(LOCO)3A") (pin "2") (pinfunction "2_2") (pintype "bidirectional"))
    )
    (net (code "117") (name "unconnected-(HERCULES(LOCO)3A-Pad4)") (class "Default")
      (node (ref "HERCULES(LOCO)3A") (pin "4") (pinfunction "4_4") (pintype "bidirectional"))
    )
    (net (code "118") (name "unconnected-(HERCULES(LOCO)3B-Pad2)") (class "Default")
      (node (ref "HERCULES(LOCO)3B") (pin "2") (pinfunction "2_2") (pintype "bidirectional"))
    )
    (net (code "119") (name "unconnected-(HERCULES(LOCO)4B-Pad2)") (class "Default")
      (node (ref "HERCULES(LOCO)4B") (pin "2") (pinfunction "2_2") (pintype "bidirectional"))
    )
    (net (code "120") (name "unconnected-(IC1-CH1-Pad2)") (class "Default")
      (node (ref "IC1") (pin "2") (pinfunction "CH1_2") (pintype "input"))
    )
    (net (code "121") (name "unconnected-(IR(LOCO)1ANALOG-Pad2)") (class "Default")
      (node (ref "IR(LOCO)1ANALOG") (pin "2") (pinfunction "2_2") (pintype "passive"))
    )
    (net (code "122") (name "unconnected-(IR(LOCO)2ANALOG-Pad2)") (class "Default")
      (node (ref "IR(LOCO)2ANALOG") (pin "2") (pinfunction "2_2") (pintype "passive"))
    )
    (net (code "123") (name "unconnected-(IRSENSOR1-Pad4)") (class "Default")
      (node (ref "IRSENSOR1") (pin "4") (pinfunction "4_4") (pintype "bidirectional"))
    )
    (net (code "124") (name "unconnected-(IRSENSOR2-Pad4)") (class "Default")
      (node (ref "IRSENSOR2") (pin "4") (pinfunction "4_4") (pintype "bidirectional"))
    )
    (net (code "125") (name "unconnected-(IRSENSOR3-Pad4)") (class "Default")
      (node (ref "IRSENSOR3") (pin "4") (pinfunction "4_4") (pintype "bidirectional"))
    )
    (net (code "126") (name "unconnected-(IRSENSOR4-Pad4)") (class "Default")
      (node (ref "IRSENSOR4") (pin "4") (pinfunction "4_4") (pintype "bidirectional"))
    )
    (net (code "127") (name "unconnected-(LCDB-Pad3)") (class "Default")
      (node (ref "LCDB") (pin "3") (pinfunction "3_3") (pintype "bidirectional"))
    )
    (net (code "128") (name "unconnected-(LCDB-Pad4)") (class "Default")
      (node (ref "LCDB") (pin "4") (pinfunction "4_4") (pintype "bidirectional"))
    )
    (net (code "129") (name "unconnected-(LCDC-Pad1)") (class "Default")
      (node (ref "LCDC") (pin "1") (pinfunction "1_1") (pintype "bidirectional"))
    )
    (net (code "130") (name "unconnected-(LCDC-Pad2)") (class "Default")
      (node (ref "LCDC") (pin "2") (pinfunction "2_2") (pintype "bidirectional"))
    )
    (net (code "131") (name "unconnected-(MPU-Pad1)") (class "Default")
      (node (ref "MPU") (pin "1") (pinfunction "1_1") (pintype "bidirectional"))
    )
    (net (code "132") (name "unconnected-(MPU-Pad2)") (class "Default")
      (node (ref "MPU") (pin "2") (pinfunction "2_2") (pintype "bidirectional"))
    )
    (net (code "133") (name "unconnected-(MPU-Pad3)") (class "Default")
      (node (ref "MPU") (pin "3") (pinfunction "3_3") (pintype "bidirectional"))
    )
    (net (code "134") (name "unconnected-(MPU-Pad4)") (class "Default")
      (node (ref "MPU") (pin "4") (pinfunction "4_4") (pintype "bidirectional"))
    )
    (net (code "135") (name "unconnected-(PCB1-3V3-PadP$1)") (class "Default")
      (node (ref "PCB1") (pin "P$1") (pinfunction "3V3_P$1") (pintype "bidirectional"))
    )
    (net (code "136") (name "unconnected-(PCB1-3V3-PadP$17)") (class "Default")
      (node (ref "PCB1") (pin "P$17") (pinfunction "3V3_P$17") (pintype "bidirectional"))
    )
    (net (code "137") (name "unconnected-(PCB1-5V-PadP$2)") (class "Default")
      (node (ref "PCB1") (pin "P$2") (pinfunction "5V_P$2") (pintype "bidirectional"))
    )
    (net (code "138") (name "unconnected-(PCB1-5V-PadP$4)") (class "Default")
      (node (ref "PCB1") (pin "P$4") (pinfunction "5V_P$4") (pintype "bidirectional"))
    )
    (net (code "139") (name "unconnected-(PCB1-GND-PadP$14)") (class "Default")
      (node (ref "PCB1") (pin "P$14") (pinfunction "GND_P$14") (pintype "bidirectional"))
    )
    (net (code "140") (name "unconnected-(PCB1-GND-PadP$20)") (class "Default")
      (node (ref "PCB1") (pin "P$20") (pinfunction "GND_P$20") (pintype "bidirectional"))
    )
    (net (code "141") (name "unconnected-(PCB1-GND-PadP$30)") (class "Default")
      (node (ref "PCB1") (pin "P$30") (pinfunction "GND_P$30") (pintype "bidirectional"))
    )
    (net (code "142") (name "unconnected-(PCB1-GND-PadP$39)") (class "Default")
      (node (ref "PCB1") (pin "P$39") (pinfunction "GND_P$39") (pintype "bidirectional"))
    )
    (net (code "143") (name "unconnected-(PCB1-GPIO8-PadP$24)") (class "Default")
      (node (ref "PCB1") (pin "P$24") (pinfunction "GPIO8_P$24") (pintype "bidirectional"))
    )
    (net (code "144") (name "unconnected-(PCB1-GPIO18-PadP$12)") (class "Default")
      (node (ref "PCB1") (pin "P$12") (pinfunction "GPIO18_P$12") (pintype "bidirectional"))
    )
    (net (code "145") (name "unconnected-(PCB1-GPIO21-PadP$40)") (class "Default")
      (node (ref "PCB1") (pin "P$40") (pinfunction "GPIO21_P$40") (pintype "bidirectional"))
    )
    (net (code "146") (name "unconnected-(PCB1-GPIO23-PadP$16)") (class "Default")
      (node (ref "PCB1") (pin "P$16") (pinfunction "GPIO23_P$16") (pintype "bidirectional"))
    )
    (net (code "147") (name "unconnected-(PCB1-GPIO24-PadP$18)") (class "Default")
      (node (ref "PCB1") (pin "P$18") (pinfunction "GPIO24_P$18") (pintype "bidirectional"))
    )
    (net (code "148") (name "unconnected-(PCB1-GPIO25-PadP$22)") (class "Default")
      (node (ref "PCB1") (pin "P$22") (pinfunction "GPIO25_P$22") (pintype "bidirectional"))
    )
    (net (code "149") (name "unconnected-(PCB1-GPIO26-PadP$37)") (class "Default")
      (node (ref "PCB1") (pin "P$37") (pinfunction "GPIO26_P$37") (pintype "bidirectional"))
    )
    (net (code "150") (name "unconnected-(PCB1-ID_SC*-PadP$28)") (class "Default")
      (node (ref "PCB1") (pin "P$28") (pinfunction "ID_SC*_P$28") (pintype "bidirectional"))
    )
    (net (code "151") (name "unconnected-(PCB1-ID_SD*-PadP$27)") (class "Default")
      (node (ref "PCB1") (pin "P$27") (pinfunction "ID_SD*_P$27") (pintype "bidirectional"))
    )
    (net (code "152") (name "unconnected-(SERVO1-Pad4)") (class "Default")
      (node (ref "SERVO1") (pin "4") (pinfunction "4_4") (pintype "bidirectional"))
    )
    (net (code "153") (name "unconnected-(SERVO2-Pad4)") (class "Default")
      (node (ref "SERVO2") (pin "4") (pinfunction "4_4") (pintype "bidirectional"))
    )
    (net (code "154") (name "unconnected-(SERVO3-Pad4)") (class "Default")
      (node (ref "SERVO3") (pin "4") (pinfunction "4_4") (pintype "bidirectional"))
    )
    (net (code "155") (name "unconnected-(SERVO4-Pad4)") (class "Default")
      (node (ref "SERVO4") (pin "4") (pinfunction "4_4") (pintype "bidirectional"))
    )
  )
)
